# Relay_Design.net
KiCad netlist of a schematic drawn in Altium Designer
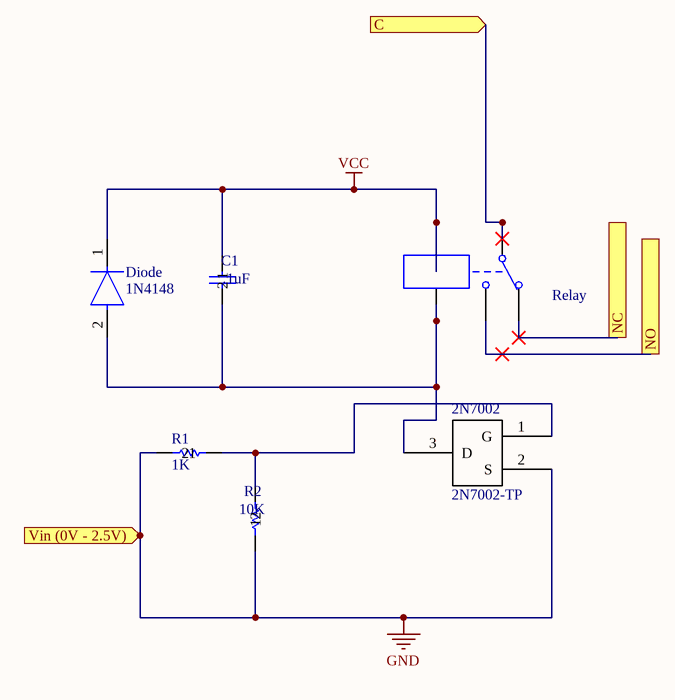
[diagram p0: Relay Design.SchDoc]

(export (version "E")
  (design (tool "Eeschema 10.0.6"))
  (components
    (comp (ref "2N7002")
      (value "2N7002-TP")
      (footprint "2N7002")
      (libsource (lib "Parts") (part "2N7002-TP"))
    )
    (comp (ref "C1")
      (value ".1uF")
      (footprint "RAD-0.3")
      (description "Capacitor")
      (fields (field (name "Comment") "Cap") (field (name "PUBLISHER") "Altium Limited"))
      (libsource (lib "Miscellaneous Devices") (part "Cap"))
    )
    (comp (ref "Diode")
      (value "1N4148")
      (footprint "FP-017AG-MFG")
      (description "DIODE GEN PURP 100V 200MA DO35")
      (fields (field (name "VOLTAGE") "100V"))
      (libsource (lib "Altium Content Vault") (part "d7152d700b627762746794eb795d46e"))
    )
    (comp (ref "R1")
      (value "1K")
      (footprint "AXIAL-0.3")
      (description "Resistor")
      (fields (field (name "Comment") "Res1") (field (name "PUBLISHER") "Altium Limited"))
      (libsource (lib "Miscellaneous Devices") (part "Res1"))
    )
    (comp (ref "R2")
      (value "10K")
      (footprint "AXIAL-0.3")
      (description "Resistor")
      (fields (field (name "Comment") "Res1") (field (name "PUBLISHER") "Altium Limited"))
      (libsource (lib "Miscellaneous Devices") (part "Res1"))
    )
    (comp (ref "Relay")
      (value "Relay-SPDT")
      (footprint "Relay")
      (description "Single-Pole Dual-Throw Relay")
      (fields (field (name "PUBLISHER") "Altium Limited"))
      (libsource (lib "Miscellaneous Devices") (part "Relay-SPDT"))
    )
  )
  (nets
    (net (code "1") (name "/C") (class "Default")
      (node (ref "Relay") (pin "1") (pinfunction "1_1") (pintype "passive+no_connect"))
    )
    (net (code "2") (name "/NC") (class "Default")
      (node (ref "Relay") (pin "2") (pinfunction "2_2") (pintype "passive+no_connect"))
    )
    (net (code "3") (name "/NO") (class "Default")
      (node (ref "Relay") (pin "3") (pinfunction "3_3") (pintype "passive"))
    )
    (net (code "4") (name "GND") (class "Default")
      (node (ref "2N7002") (pin "2") (pinfunction "S_2") (pintype "passive"))
      (node (ref "R1") (pin "2") (pinfunction "2_2") (pintype "passive"))
      (node (ref "R2") (pin "1") (pinfunction "1_1") (pintype "passive"))
    )
    (net (code "5") (name "Net-(2N7002-D)") (class "Default")
      (node (ref "2N7002") (pin "3") (pinfunction "D_3") (pintype "passive"))
      (node (ref "C1") (pin "1") (pinfunction "1_1") (pintype "passive"))
      (node (ref "Diode") (pin "2") (pinfunction "A_2") (pintype "passive"))
      (node (ref "Relay") (pin "5") (pinfunction "5_5") (pintype "passive"))
    )
    (net (code "6") (name "Net-(2N7002-G)") (class "Default")
      (node (ref "2N7002") (pin "1") (pinfunction "G_1") (pintype "passive"))
      (node (ref "R1") (pin "1") (pinfunction "1_1") (pintype "passive"))
      (node (ref "R2") (pin "2") (pinfunction "2_2") (pintype "passive"))
    )
    (net (code "7") (name "VCC") (class "Default")
      (node (ref "C1") (pin "2") (pinfunction "2_2") (pintype "passive"))
      (node (ref "Diode") (pin "1") (pinfunction "C_1") (pintype "passive"))
      (node (ref "Relay") (pin "4") (pinfunction "4_4") (pintype "passive"))
    )
  )
)
